# 10ACurrentSensor.net
KiCad netlist of a schematic drawn in Altium Designer
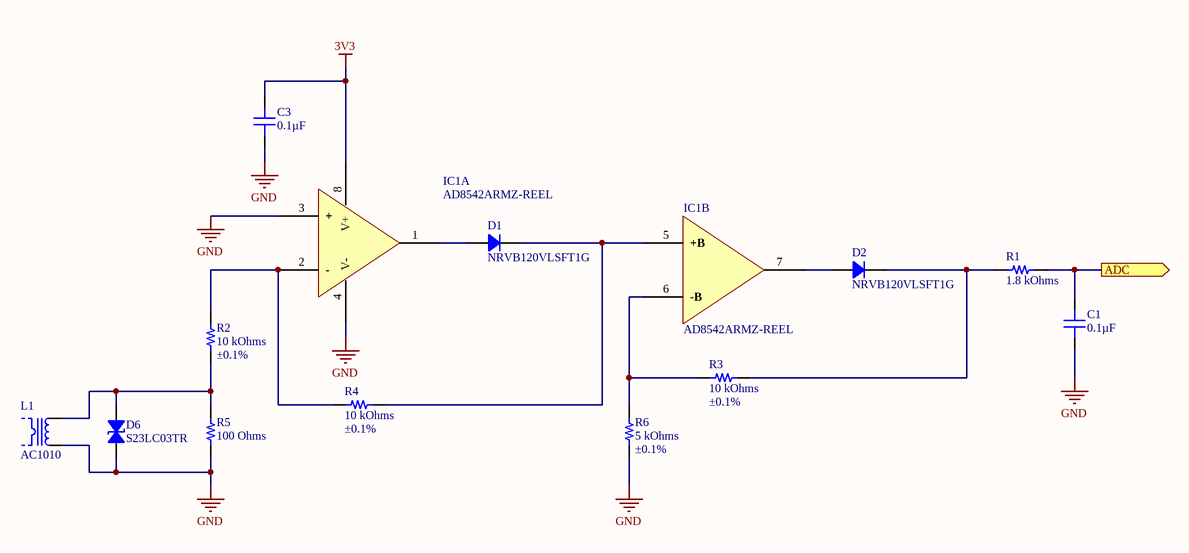
[diagram p0: 10ACurrentSensor.SchDoc]

(export (version "E")
  (design (tool "Eeschema 10.0.6"))
  (components
    (comp (ref "C1")
      (value "0.1µF")
      (footprint "CAP 0603_1608")
      (description "CAP CER 0.1UF 16V X7R 0603")
      (fields (field (name "PART NUMBER") "CS0603KRX7R7BB104") (field (name "MANUFACTURER") "Yageo"))
      (libsource (lib "Celestial Altium Library - altium_library") (part "Capacitor"))
    )
    (comp (ref "C3")
      (value "0.1µF")
      (footprint "CAP 0603_1608")
      (description "CAP CER 0.1UF 16V X7R 0603")
      (fields (field (name "PART NUMBER") "CS0603KRX7R7BB104") (field (name "MANUFACTURER") "Yageo"))
      (libsource (lib "Celestial Altium Library - altium_library") (part "Capacitor"))
    )
    (comp (ref "D1")
      (value "NRVB120VLSFT1G")
      (footprint "SOD123F")
      (description "DIODE SCHOTTKY 20V 1A SOD123")
      (fields (field (name "MANUFACTURER") "ON Semiconductor"))
      (libsource (lib "Celestial Altium Library - altium_library") (part "Diode"))
    )
    (comp (ref "D2")
      (value "NRVB120VLSFT1G")
      (footprint "SOD123F")
      (description "DIODE SCHOTTKY 20V 1A SOD123")
      (fields (field (name "MANUFACTURER") "ON Semiconductor"))
      (libsource (lib "Celestial Altium Library - altium_library") (part "Diode"))
    )
    (comp (ref "D6")
      (value "S23LC03TR")
      (footprint "DIODES SOT-23-3")
      (description "TVS DIODE 3.3V 8V SOT23")
      (fields (field (name "MANUFACTURER") "SMC Diode Solutions"))
      (libsource (lib "Celestial Altium Library - altium_library") (part "Diode TVS"))
    )
    (comp (ref "IC1")
      (value "AD8542ARMZ-REEL")
      (footprint "ANALOG MSOP-8 RM-8")
      (description "IC OPAMP GP 2 CIRCUIT 8MSOP")
      (fields (field (name "MANUFACTURER") "Analog Devices Inc."))
      (libsource (lib "Celestial Altium Library - altium_library") (part "ANALOG DEV AD8542"))
    )
    (comp (ref "L1")
      (value "AC1010")
      (footprint "TALEMA AC1010")
      (description "CURR SENSE XFMR 10A T/H")
      (fields (field (name "MANUFACTURER") "Talema Group LLC"))
      (libsource (lib "Celestial Altium Library - altium_library") (part "TALEMA AC1xxx"))
    )
    (comp (ref "R1")
      (value "1.8 kOhms")
      (footprint "RES 0603_1608")
      (description "RES 1.8K OHM 5% 1/10W 0603")
      (fields
        (field (name "PART NUMBER") "RMCF0603JT1K80")
        (field (name "MANUFACTURER") "Stackpole Electronics Inc")
      )
      (libsource (lib "Celestial Altium Library - altium_library") (part "Resistor"))
    )
    (comp (ref "R2")
      (value "10 kOhms")
      (footprint "RES 0603_1608")
      (description "RES SMD 10K OHM 0.1% 1/10W 0603")
      (fields
        (field (name "PART NUMBER") "ERA-3AEB103V")
        (field (name "MANUFACTURER") "Panasonic Electronic Components")
        (field (name "TOLERANCE") "±0.1%")
      )
      (libsource (lib "Celestial Altium Library - altium_library") (part "Resistor"))
    )
    (comp (ref "R3")
      (value "10 kOhms")
      (footprint "RES 0603_1608")
      (description "RES SMD 10K OHM 0.1% 1/10W 0603")
      (fields
        (field (name "PART NUMBER") "ERA-3AEB103V")
        (field (name "MANUFACTURER") "Panasonic Electronic Components")
        (field (name "TOLERANCE") "±0.1%")
      )
      (libsource (lib "Celestial Altium Library - altium_library") (part "Resistor"))
    )
    (comp (ref "R4")
      (value "10 kOhms")
      (footprint "RES 0603_1608")
      (description "RES SMD 10K OHM 0.1% 1/10W 0603")
      (fields
        (field (name "PART NUMBER") "ERA-3AEB103V")
        (field (name "MANUFACTURER") "Panasonic Electronic Components")
        (field (name "TOLERANCE") "±0.1%")
      )
      (libsource (lib "Celestial Altium Library - altium_library") (part "Resistor"))
    )
    (comp (ref "R5")
      (value "100 Ohms")
      (footprint "RES 0603_1608")
      (description "RES SMD 100 OHM 5% 1/4W 0603")
      (fields (field (name "PART NUMBER") "ESR03EZPJ101") (field (name "MANUFACTURER") "Rohm Semiconductor"))
      (libsource (lib "Celestial Altium Library - altium_library") (part "Resistor"))
    )
    (comp (ref "R6")
      (value "5 kOhms")
      (footprint "RES 0603_1608")
      (description "RES SMD 5K OHM 0.1% 0.15W 0603")
      (fields
        (field (name "PART NUMBER") "PNM0603E5001BST5")
        (field (name "MANUFACTURER") "Vishay Thin Film")
        (field (name "TOLERANCE") "±0.1%")
      )
      (libsource (lib "Celestial Altium Library - altium_library") (part "Resistor"))
    )
  )
  (nets
    (net (code "1") (name "/ADC") (class "Default")
      (node (ref "C1") (pin "2") (pinfunction "2_2") (pintype "passive"))
      (node (ref "R1") (pin "2") (pinfunction "2_2") (pintype "passive"))
    )
    (net (code "2") (name "3V3") (class "Default")
      (node (ref "C3") (pin "2") (pinfunction "2_2") (pintype "passive"))
      (node (ref "IC1") (pin "8") (pinfunction "V+_8") (pintype "passive"))
    )
    (net (code "3") (name "GND") (class "Default")
      (node (ref "C1") (pin "1") (pinfunction "1_1") (pintype "passive"))
      (node (ref "C3") (pin "1") (pinfunction "1_1") (pintype "passive"))
      (node (ref "D6") (pin "1") (pinfunction "1_1") (pintype "passive"))
      (node (ref "IC1") (pin "3") (pinfunction "+_3") (pintype "passive"))
      (node (ref "IC1") (pin "4") (pinfunction "V-_4") (pintype "passive"))
      (node (ref "L1") (pin "1") (pinfunction "1_1") (pintype "passive"))
      (node (ref "R5") (pin "1") (pinfunction "1_1") (pintype "passive"))
      (node (ref "R6") (pin "2") (pinfunction "2_2") (pintype "passive"))
    )
    (net (code "4") (name "Net-(D2-Pad2)") (class "Default")
      (node (ref "D2") (pin "2") (pinfunction "2_2") (pintype "passive"))
      (node (ref "R1") (pin "1") (pinfunction "1_1") (pintype "passive"))
      (node (ref "R3") (pin "1") (pinfunction "1_1") (pintype "passive"))
    )
    (net (code "5") (name "Net-(D6-Pad2)") (class "Default")
      (node (ref "D6") (pin "2") (pinfunction "2_2") (pintype "passive"))
      (node (ref "L1") (pin "2") (pinfunction "2_2") (pintype "passive"))
      (node (ref "R2") (pin "1") (pinfunction "1_1") (pintype "passive"))
      (node (ref "R5") (pin "2") (pinfunction "2_2") (pintype "passive"))
    )
    (net (code "6") (name "Net-(IC1A--)") (class "Default")
      (node (ref "IC1") (pin "2") (pinfunction "-_2") (pintype "passive"))
      (node (ref "R2") (pin "2") (pinfunction "2_2") (pintype "passive"))
      (node (ref "R4") (pin "2") (pinfunction "2_2") (pintype "passive"))
    )
    (net (code "7") (name "Net-(IC1A-OUT)") (class "Default")
      (node (ref "D1") (pin "1") (pinfunction "1_1") (pintype "passive"))
      (node (ref "IC1") (pin "1") (pinfunction "OUT_1") (pintype "passive"))
    )
    (net (code "8") (name "Net-(IC1B-+B)") (class "Default")
      (node (ref "D1") (pin "2") (pinfunction "2_2") (pintype "passive"))
      (node (ref "IC1") (pin "5") (pinfunction "+B_5") (pintype "passive"))
      (node (ref "R4") (pin "1") (pinfunction "1_1") (pintype "passive"))
    )
    (net (code "9") (name "Net-(IC1B--B)") (class "Default")
      (node (ref "IC1") (pin "6") (pinfunction "-B_6") (pintype "passive"))
      (node (ref "R3") (pin "2") (pinfunction "2_2") (pintype "passive"))
      (node (ref "R6") (pin "1") (pinfunction "1_1") (pintype "passive"))
    )
    (net (code "10") (name "Net-(IC1B-OUT_B)") (class "Default")
      (node (ref "D2") (pin "1") (pinfunction "1_1") (pintype "passive"))
      (node (ref "IC1") (pin "7") (pinfunction "OUT_B_7") (pintype "passive"))
    )
  )
)
